# PSRAM.net
KiCad netlist of a schematic drawn in Altium Designer
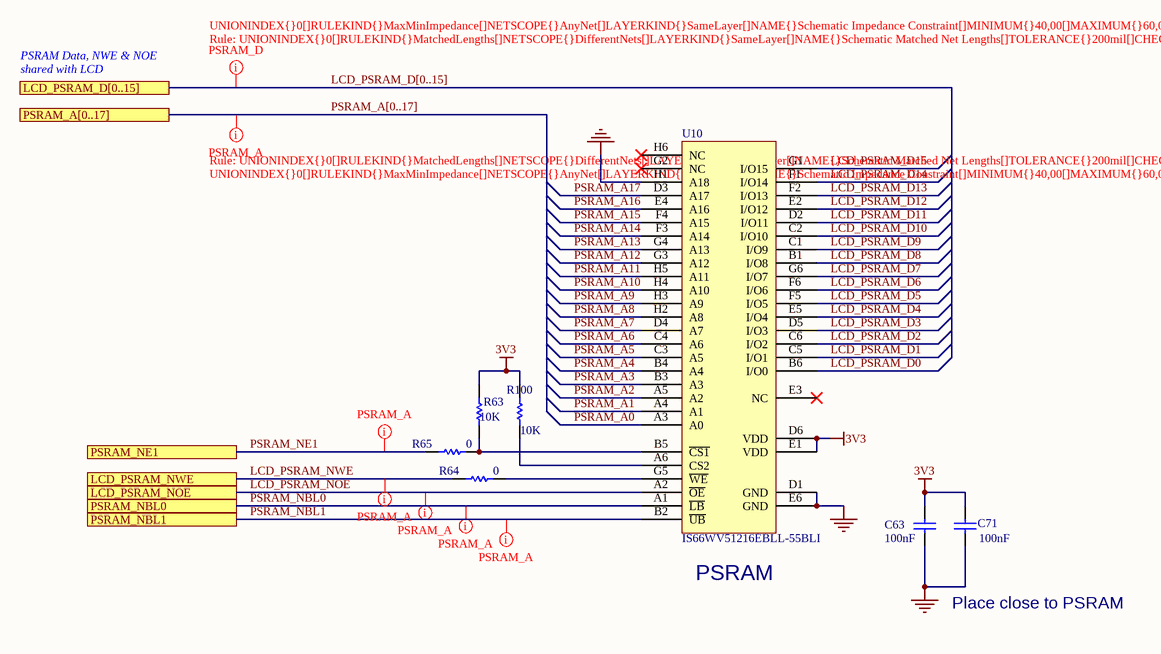
[diagram p0: PSRAM.SchDoc]

(export (version "E")
  (design (tool "Eeschema 10.0.6"))
  (components
    (comp (ref "C63")
      (value "100nF")
      (footprint "0402C")
      (description "Capacitor,100nF,16V,X7R,10%,0402,YAGEO")
      (libsource (lib "MCD_TOOLS") (part "Cap_100nF_X7R_10%_0402"))
    )
    (comp (ref "C71")
      (value "100nF")
      (footprint "0402C")
      (description "Capacitor,100nF,16V,X7R,10%,0402,YAGEO")
      (libsource (lib "MCD_TOOLS") (part "Cap_100nF_X7R_10%_0402"))
    )
    (comp (ref "R63")
      (value "10K")
      (footprint "0603R")
      (description "Resistor,10K,0603,1%,YAGEO")
      (fields (field (name "Comment") "10K_1%_0603"))
      (libsource (lib "MCD_TOOLS_RESISTOR") (part "Res_10K_1%_0603"))
    )
    (comp (ref "R64")
      (value "0")
      (footprint "0603R-GS")
      (description "Resistor,0,0603,5%,YAGEO")
      (fields (field (name "Comment") "0_5%_0603"))
      (libsource (lib "MCD_TOOLS_RESISTOR") (part "Res_0_5%_0603"))
    )
    (comp (ref "R65")
      (value "0")
      (footprint "0603R-GS")
      (description "Resistor,0,0603,5%,YAGEO")
      (fields (field (name "Comment") "0_5%_0603"))
      (libsource (lib "MCD_TOOLS_RESISTOR") (part "Res_0_5%_0603"))
    )
    (comp (ref "R100")
      (value "10K")
      (footprint "0603R")
      (description "Resistor,10K,0603,1%,YAGEO")
      (fields (field (name "Comment") "10K_1%_0603"))
      (libsource (lib "MCD_TOOLS_RESISTOR") (part "Res_10K_1%_0603"))
    )
    (comp (ref "U10")
      (value "IS66WV51216EBLL-55BLI")
      (footprint "FBGA48_0R75_6X8")
      (description "IC SRAM 8MBIT 55NS 48MINIBGA 6mm x 8mm")
      (libsource (lib "MCD_TEMP_NPA") (part "IS66WV51216EBLL-55BLI"))
    )
  )
  (nets
    (net (code "1") (name "/LCD_PSRAM_D0") (class "Default")
      (node (ref "U10") (pin "B6") (pinfunction "I/O0_B6") (pintype "passive"))
    )
    (net (code "2") (name "/LCD_PSRAM_D1") (class "Default")
      (node (ref "U10") (pin "C5") (pinfunction "I/O1_C5") (pintype "passive"))
    )
    (net (code "3") (name "/LCD_PSRAM_D2") (class "Default")
      (node (ref "U10") (pin "C6") (pinfunction "I/O2_C6") (pintype "passive"))
    )
    (net (code "4") (name "/LCD_PSRAM_D3") (class "Default")
      (node (ref "U10") (pin "D5") (pinfunction "I/O3_D5") (pintype "passive"))
    )
    (net (code "5") (name "/LCD_PSRAM_D4") (class "Default")
      (node (ref "U10") (pin "E5") (pinfunction "I/O4_E5") (pintype "passive"))
    )
    (net (code "6") (name "/LCD_PSRAM_D5") (class "Default")
      (node (ref "U10") (pin "F5") (pinfunction "I/O5_F5") (pintype "passive"))
    )
    (net (code "7") (name "/LCD_PSRAM_D6") (class "Default")
      (node (ref "U10") (pin "F6") (pinfunction "I/O6_F6") (pintype "passive"))
    )
    (net (code "8") (name "/LCD_PSRAM_D7") (class "Default")
      (node (ref "U10") (pin "G6") (pinfunction "I/O7_G6") (pintype "passive"))
    )
    (net (code "9") (name "/LCD_PSRAM_D8") (class "Default")
      (node (ref "U10") (pin "B1") (pinfunction "I/O8_B1") (pintype "passive"))
    )
    (net (code "10") (name "/LCD_PSRAM_D9") (class "Default")
      (node (ref "U10") (pin "C1") (pinfunction "I/O9_C1") (pintype "passive"))
    )
    (net (code "11") (name "/LCD_PSRAM_D10") (class "Default")
      (node (ref "U10") (pin "C2") (pinfunction "I/O10_C2") (pintype "passive"))
    )
    (net (code "12") (name "/LCD_PSRAM_D11") (class "Default")
      (node (ref "U10") (pin "D2") (pinfunction "I/O11_D2") (pintype "passive"))
    )
    (net (code "13") (name "/LCD_PSRAM_D12") (class "Default")
      (node (ref "U10") (pin "E2") (pinfunction "I/O12_E2") (pintype "passive"))
    )
    (net (code "14") (name "/LCD_PSRAM_D13") (class "Default")
      (node (ref "U10") (pin "F2") (pinfunction "I/O13_F2") (pintype "passive"))
    )
    (net (code "15") (name "/LCD_PSRAM_D14") (class "Default")
      (node (ref "U10") (pin "F1") (pinfunction "I/O14_F1") (pintype "passive"))
    )
    (net (code "16") (name "/LCD_PSRAM_D15") (class "Default")
      (node (ref "U10") (pin "G1") (pinfunction "I/O15_G1") (pintype "passive"))
    )
    (net (code "18") (name "/LCD_PSRAM_NOE") (class "Default")
      (node (ref "U10") (pin "A2") (pinfunction "~{OE}_A2") (pintype "passive"))
    )
    (net (code "19") (name "/LCD_PSRAM_NWE") (class "Default")
      (node (ref "R64") (pin "1") (pinfunction "1_1") (pintype "passive"))
    )
    (net (code "20") (name "/PSRAM_A0") (class "Default")
      (node (ref "U10") (pin "A3") (pinfunction "A0_A3") (pintype "passive"))
    )
    (net (code "21") (name "/PSRAM_A1") (class "Default")
      (node (ref "U10") (pin "A4") (pinfunction "A1_A4") (pintype "passive"))
    )
    (net (code "22") (name "/PSRAM_A2") (class "Default")
      (node (ref "U10") (pin "A5") (pinfunction "A2_A5") (pintype "passive"))
    )
    (net (code "23") (name "/PSRAM_A3") (class "Default")
      (node (ref "U10") (pin "B3") (pinfunction "A3_B3") (pintype "passive"))
    )
    (net (code "24") (name "/PSRAM_A4") (class "Default")
      (node (ref "U10") (pin "B4") (pinfunction "A4_B4") (pintype "passive"))
    )
    (net (code "25") (name "/PSRAM_A5") (class "Default")
      (node (ref "U10") (pin "C3") (pinfunction "A5_C3") (pintype "passive"))
    )
    (net (code "26") (name "/PSRAM_A6") (class "Default")
      (node (ref "U10") (pin "C4") (pinfunction "A6_C4") (pintype "passive"))
    )
    (net (code "27") (name "/PSRAM_A7") (class "Default")
      (node (ref "U10") (pin "D4") (pinfunction "A7_D4") (pintype "passive"))
    )
    (net (code "28") (name "/PSRAM_A8") (class "Default")
      (node (ref "U10") (pin "H2") (pinfunction "A8_H2") (pintype "passive"))
    )
    (net (code "29") (name "/PSRAM_A9") (class "Default")
      (node (ref "U10") (pin "H3") (pinfunction "A9_H3") (pintype "passive"))
    )
    (net (code "30") (name "/PSRAM_A10") (class "Default")
      (node (ref "U10") (pin "H4") (pinfunction "A10_H4") (pintype "passive"))
    )
    (net (code "31") (name "/PSRAM_A11") (class "Default")
      (node (ref "U10") (pin "H5") (pinfunction "A11_H5") (pintype "passive"))
    )
    (net (code "32") (name "/PSRAM_A12") (class "Default")
      (node (ref "U10") (pin "G3") (pinfunction "A12_G3") (pintype "passive"))
    )
    (net (code "33") (name "/PSRAM_A13") (class "Default")
      (node (ref "U10") (pin "G4") (pinfunction "A13_G4") (pintype "passive"))
    )
    (net (code "34") (name "/PSRAM_A14") (class "Default")
      (node (ref "U10") (pin "F3") (pinfunction "A14_F3") (pintype "passive"))
    )
    (net (code "35") (name "/PSRAM_A15") (class "Default")
      (node (ref "U10") (pin "F4") (pinfunction "A15_F4") (pintype "passive"))
    )
    (net (code "36") (name "/PSRAM_A16") (class "Default")
      (node (ref "U10") (pin "E4") (pinfunction "A16_E4") (pintype "passive"))
    )
    (net (code "37") (name "/PSRAM_A17") (class "Default")
      (node (ref "U10") (pin "D3") (pinfunction "A17_D3") (pintype "passive"))
    )
    (net (code "39") (name "/PSRAM_NBL0") (class "Default")
      (node (ref "U10") (pin "A1") (pinfunction "~{LB}_A1") (pintype "passive"))
    )
    (net (code "40") (name "/PSRAM_NBL1") (class "Default")
      (node (ref "U10") (pin "B2") (pinfunction "~{UB}_B2") (pintype "passive"))
    )
    (net (code "41") (name "/PSRAM_NE1") (class "Default")
      (node (ref "R65") (pin "1") (pinfunction "1_1") (pintype "passive"))
    )
    (net (code "42") (name "3V3") (class "Default")
      (node (ref "C63") (pin "2") (pinfunction "2_2") (pintype "passive"))
      (node (ref "C71") (pin "2") (pinfunction "2_2") (pintype "passive"))
      (node (ref "R100") (pin "2") (pinfunction "2_2") (pintype "passive"))
      (node (ref "R63") (pin "2") (pinfunction "2_2") (pintype "passive"))
      (node (ref "U10") (pin "D6") (pinfunction "VDD_D6") (pintype "passive"))
      (node (ref "U10") (pin "E1") (pinfunction "VDD_E1") (pintype "passive"))
    )
    (net (code "43") (name "GND") (class "Default")
      (node (ref "C63") (pin "1") (pinfunction "1_1") (pintype "passive"))
      (node (ref "C71") (pin "1") (pinfunction "1_1") (pintype "passive"))
      (node (ref "U10") (pin "D1") (pinfunction "GND_D1") (pintype "passive"))
      (node (ref "U10") (pin "E6") (pinfunction "GND_E6") (pintype "passive"))
      (node (ref "U10") (pin "H1") (pinfunction "A18_H1") (pintype "passive"))
    )
    (net (code "44") (name "Net-(U10-CS2)") (class "Default")
      (node (ref "R100") (pin "1") (pinfunction "1_1") (pintype "passive"))
      (node (ref "U10") (pin "A6") (pinfunction "CS2_A6") (pintype "passive"))
    )
    (net (code "45") (name "Net-(U10-~{CS1})") (class "Default")
      (node (ref "R63") (pin "1") (pinfunction "1_1") (pintype "passive"))
      (node (ref "R65") (pin "2") (pinfunction "2_2") (pintype "passive"))
      (node (ref "U10") (pin "B5") (pinfunction "~{CS1}_B5") (pintype "passive"))
    )
    (net (code "46") (name "Net-(U10-~{WE})") (class "Default")
      (node (ref "R64") (pin "2") (pinfunction "2_2") (pintype "passive"))
      (node (ref "U10") (pin "G5") (pinfunction "~{WE}_G5") (pintype "passive"))
    )
    (net (code "47") (name "unconnected-(U10-NC-PadE3)") (class "Default")
      (node (ref "U10") (pin "E3") (pinfunction "NC_E3") (pintype "passive+no_connect"))
    )
    (net (code "48") (name "unconnected-(U10-NC-PadG2)") (class "Default")
      (node (ref "U10") (pin "G2") (pinfunction "NC_G2") (pintype "passive+no_connect"))
    )
    (net (code "49") (name "unconnected-(U10-NC-PadH6)") (class "Default")
      (node (ref "U10") (pin "H6") (pinfunction "NC_H6") (pintype "passive+no_connect"))
    )
  )
)
